# SrcBackplane01_7slots.net
KiCad netlist of a schematic drawn in EAGLE
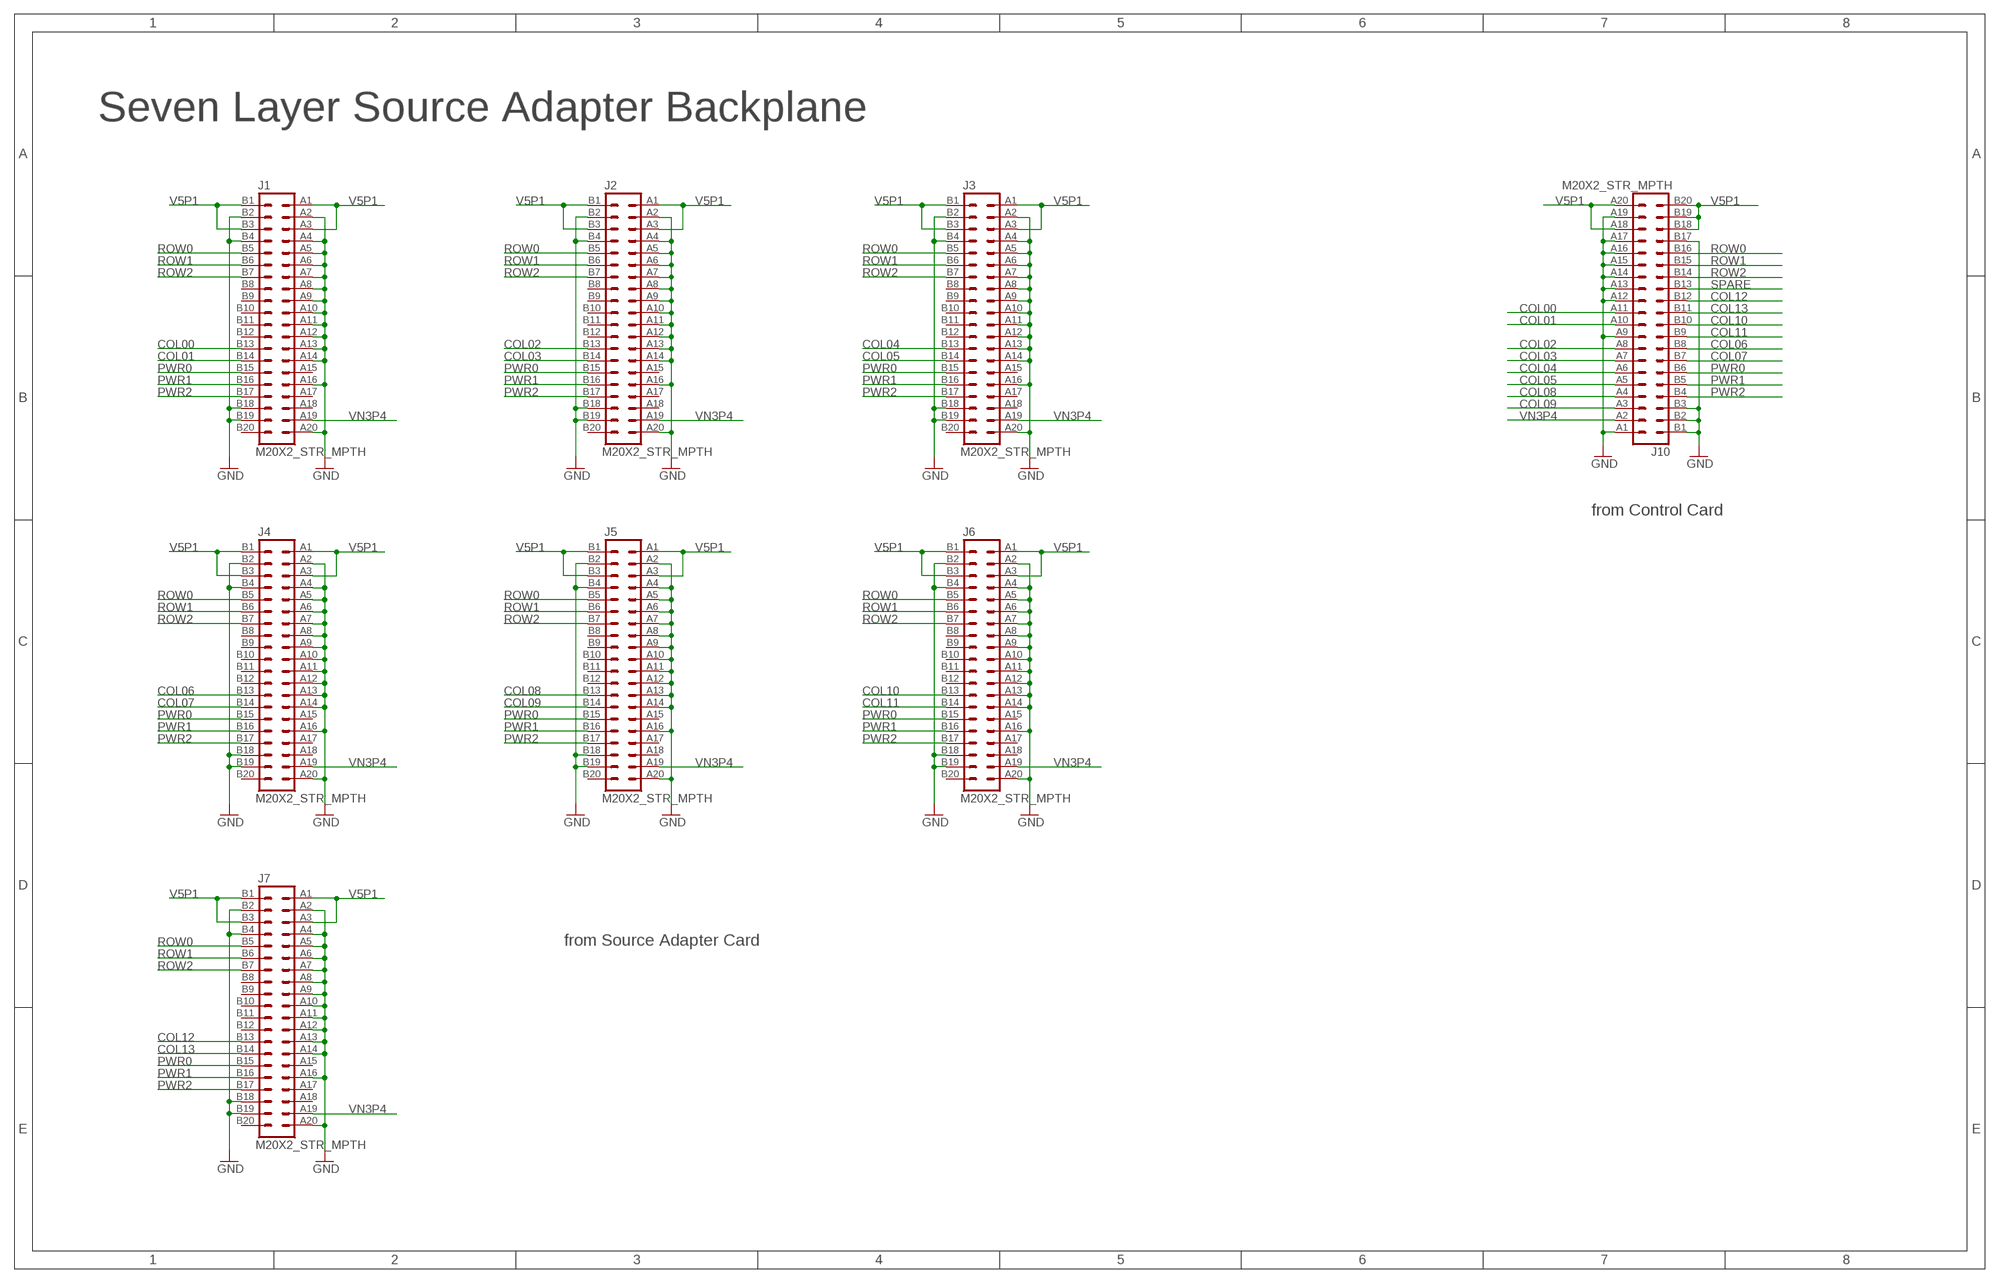
[diagram p0: schematic, sheet 1]

(export (version "E")
  (design (tool "Eeschema 10.0.6"))
  (components
    (comp (ref "J1")
      (value "M20X2_STR_MPTH")
      (footprint "eagle-import:M20X2_HARFLEX_F_STR_MPTH")
      (libsource (lib "eagle-import") (part "M20X2_STR_MPTH"))
    )
    (comp (ref "J2")
      (value "M20X2_STR_MPTH")
      (footprint "eagle-import:M20X2_HARFLEX_F_STR_MPTH")
      (libsource (lib "eagle-import") (part "M20X2_STR_MPTH"))
    )
    (comp (ref "J3")
      (value "M20X2_STR_MPTH")
      (footprint "eagle-import:M20X2_HARFLEX_F_STR_MPTH")
      (libsource (lib "eagle-import") (part "M20X2_STR_MPTH"))
    )
    (comp (ref "J4")
      (value "M20X2_STR_MPTH")
      (footprint "eagle-import:M20X2_HARFLEX_F_STR_MPTH")
      (libsource (lib "eagle-import") (part "M20X2_STR_MPTH"))
    )
    (comp (ref "J5")
      (value "M20X2_STR_MPTH")
      (footprint "eagle-import:M20X2_HARFLEX_F_STR_MPTH")
      (libsource (lib "eagle-import") (part "M20X2_STR_MPTH"))
    )
    (comp (ref "J6")
      (value "M20X2_STR_MPTH")
      (footprint "eagle-import:M20X2_HARFLEX_F_STR_MPTH")
      (libsource (lib "eagle-import") (part "M20X2_STR_MPTH"))
    )
    (comp (ref "J7")
      (value "M20X2_STR_MPTH")
      (footprint "eagle-import:M20X2_HARFLEX_F_STR_MPTH")
      (libsource (lib "eagle-import") (part "M20X2_STR_MPTH"))
    )
    (comp (ref "J10")
      (value "M20X2_STR_MPTH")
      (footprint "eagle-import:M20X2_HARFLEX_F_STR_MPTH")
      (libsource (lib "eagle-import") (part "M20X2_STR_MPTH"))
    )
  )
  (nets
    (net (code "1") (name "/COL00") (class "Default")
      (node (ref "J1") (pin "B13") (pinfunction "25_B13") (pintype "passive"))
      (node (ref "J10") (pin "A11") (pinfunction "22_A11") (pintype "passive"))
    )
    (net (code "2") (name "/COL01") (class "Default")
      (node (ref "J1") (pin "B14") (pinfunction "27_B14") (pintype "passive"))
      (node (ref "J10") (pin "A10") (pinfunction "20_A10") (pintype "passive"))
    )
    (net (code "3") (name "/COL02") (class "Default")
      (node (ref "J10") (pin "A8") (pinfunction "16_A8") (pintype "passive"))
      (node (ref "J2") (pin "B13") (pinfunction "25_B13") (pintype "passive"))
    )
    (net (code "4") (name "/COL03") (class "Default")
      (node (ref "J10") (pin "A7") (pinfunction "14_A7") (pintype "passive"))
      (node (ref "J2") (pin "B14") (pinfunction "27_B14") (pintype "passive"))
    )
    (net (code "5") (name "/COL04") (class "Default")
      (node (ref "J10") (pin "A6") (pinfunction "12_A6") (pintype "passive"))
      (node (ref "J3") (pin "B13") (pinfunction "25_B13") (pintype "passive"))
    )
    (net (code "6") (name "/COL05") (class "Default")
      (node (ref "J10") (pin "A5") (pinfunction "10_A5") (pintype "passive"))
      (node (ref "J3") (pin "B14") (pinfunction "27_B14") (pintype "passive"))
    )
    (net (code "7") (name "/COL06") (class "Default")
      (node (ref "J10") (pin "B8") (pinfunction "15_B8") (pintype "passive"))
      (node (ref "J4") (pin "B13") (pinfunction "25_B13") (pintype "passive"))
    )
    (net (code "8") (name "/COL07") (class "Default")
      (node (ref "J10") (pin "B7") (pinfunction "13_B7") (pintype "passive"))
      (node (ref "J4") (pin "B14") (pinfunction "27_B14") (pintype "passive"))
    )
    (net (code "9") (name "/COL08") (class "Default")
      (node (ref "J10") (pin "A4") (pinfunction "8_A4") (pintype "passive"))
      (node (ref "J5") (pin "B13") (pinfunction "25_B13") (pintype "passive"))
    )
    (net (code "10") (name "/COL09") (class "Default")
      (node (ref "J10") (pin "A3") (pinfunction "6_A3") (pintype "passive"))
      (node (ref "J5") (pin "B14") (pinfunction "27_B14") (pintype "passive"))
    )
    (net (code "11") (name "/COL10") (class "Default")
      (node (ref "J10") (pin "B10") (pinfunction "19_B10") (pintype "passive"))
      (node (ref "J6") (pin "B13") (pinfunction "25_B13") (pintype "passive"))
    )
    (net (code "12") (name "/COL11") (class "Default")
      (node (ref "J10") (pin "B9") (pinfunction "17_B9") (pintype "passive"))
      (node (ref "J6") (pin "B14") (pinfunction "27_B14") (pintype "passive"))
    )
    (net (code "13") (name "/COL12") (class "Default")
      (node (ref "J10") (pin "B12") (pinfunction "23_B12") (pintype "passive"))
      (node (ref "J7") (pin "B13") (pinfunction "25_B13") (pintype "passive"))
    )
    (net (code "14") (name "/COL13") (class "Default")
      (node (ref "J10") (pin "B11") (pinfunction "21_B11") (pintype "passive"))
      (node (ref "J7") (pin "B14") (pinfunction "27_B14") (pintype "passive"))
    )
    (net (code "15") (name "/PWR0") (class "Default")
      (node (ref "J1") (pin "B15") (pinfunction "29_B15") (pintype "passive"))
      (node (ref "J10") (pin "B6") (pinfunction "11_B6") (pintype "passive"))
      (node (ref "J2") (pin "B15") (pinfunction "29_B15") (pintype "passive"))
      (node (ref "J3") (pin "B15") (pinfunction "29_B15") (pintype "passive"))
      (node (ref "J4") (pin "B15") (pinfunction "29_B15") (pintype "passive"))
      (node (ref "J5") (pin "B15") (pinfunction "29_B15") (pintype "passive"))
      (node (ref "J6") (pin "B15") (pinfunction "29_B15") (pintype "passive"))
      (node (ref "J7") (pin "B15") (pinfunction "29_B15") (pintype "passive"))
    )
    (net (code "16") (name "/PWR1") (class "Default")
      (node (ref "J1") (pin "B16") (pinfunction "31_B16") (pintype "passive"))
      (node (ref "J10") (pin "B5") (pinfunction "9_B5") (pintype "passive"))
      (node (ref "J2") (pin "B16") (pinfunction "31_B16") (pintype "passive"))
      (node (ref "J3") (pin "B16") (pinfunction "31_B16") (pintype "passive"))
      (node (ref "J4") (pin "B16") (pinfunction "31_B16") (pintype "passive"))
      (node (ref "J5") (pin "B16") (pinfunction "31_B16") (pintype "passive"))
      (node (ref "J6") (pin "B16") (pinfunction "31_B16") (pintype "passive"))
      (node (ref "J7") (pin "B16") (pinfunction "31_B16") (pintype "passive"))
    )
    (net (code "17") (name "/PWR2") (class "Default")
      (node (ref "J1") (pin "B17") (pinfunction "33_B17") (pintype "passive"))
      (node (ref "J10") (pin "B4") (pinfunction "7_B4") (pintype "passive"))
      (node (ref "J2") (pin "B17") (pinfunction "33_B17") (pintype "passive"))
      (node (ref "J3") (pin "B17") (pinfunction "33_B17") (pintype "passive"))
      (node (ref "J4") (pin "B17") (pinfunction "33_B17") (pintype "passive"))
      (node (ref "J5") (pin "B17") (pinfunction "33_B17") (pintype "passive"))
      (node (ref "J6") (pin "B17") (pinfunction "33_B17") (pintype "passive"))
      (node (ref "J7") (pin "B17") (pinfunction "33_B17") (pintype "passive"))
    )
    (net (code "18") (name "/ROW0") (class "Default")
      (node (ref "J1") (pin "B5") (pinfunction "9_B5") (pintype "passive"))
      (node (ref "J10") (pin "B16") (pinfunction "31_B16") (pintype "passive"))
      (node (ref "J2") (pin "B5") (pinfunction "9_B5") (pintype "passive"))
      (node (ref "J3") (pin "B5") (pinfunction "9_B5") (pintype "passive"))
      (node (ref "J4") (pin "B5") (pinfunction "9_B5") (pintype "passive"))
      (node (ref "J5") (pin "B5") (pinfunction "9_B5") (pintype "passive"))
      (node (ref "J6") (pin "B5") (pinfunction "9_B5") (pintype "passive"))
      (node (ref "J7") (pin "B5") (pinfunction "9_B5") (pintype "passive"))
    )
    (net (code "19") (name "/ROW1") (class "Default")
      (node (ref "J1") (pin "B6") (pinfunction "11_B6") (pintype "passive"))
      (node (ref "J10") (pin "B15") (pinfunction "29_B15") (pintype "passive"))
      (node (ref "J2") (pin "B6") (pinfunction "11_B6") (pintype "passive"))
      (node (ref "J3") (pin "B6") (pinfunction "11_B6") (pintype "passive"))
      (node (ref "J4") (pin "B6") (pinfunction "11_B6") (pintype "passive"))
      (node (ref "J5") (pin "B6") (pinfunction "11_B6") (pintype "passive"))
      (node (ref "J6") (pin "B6") (pinfunction "11_B6") (pintype "passive"))
      (node (ref "J7") (pin "B6") (pinfunction "11_B6") (pintype "passive"))
    )
    (net (code "20") (name "/ROW2") (class "Default")
      (node (ref "J1") (pin "B7") (pinfunction "13_B7") (pintype "passive"))
      (node (ref "J10") (pin "B14") (pinfunction "27_B14") (pintype "passive"))
      (node (ref "J2") (pin "B7") (pinfunction "13_B7") (pintype "passive"))
      (node (ref "J3") (pin "B7") (pinfunction "13_B7") (pintype "passive"))
      (node (ref "J4") (pin "B7") (pinfunction "13_B7") (pintype "passive"))
      (node (ref "J5") (pin "B7") (pinfunction "13_B7") (pintype "passive"))
      (node (ref "J6") (pin "B7") (pinfunction "13_B7") (pintype "passive"))
      (node (ref "J7") (pin "B7") (pinfunction "13_B7") (pintype "passive"))
    )
    (net (code "21") (name "/SPARE") (class "Default")
      (node (ref "J10") (pin "B13") (pinfunction "25_B13") (pintype "passive"))
    )
    (net (code "22") (name "/V5P1") (class "Default")
      (node (ref "J1") (pin "A1") (pinfunction "2_A1") (pintype "passive"))
      (node (ref "J1") (pin "A3") (pinfunction "6_A3") (pintype "passive"))
      (node (ref "J1") (pin "B1") (pinfunction "1_B1") (pintype "passive"))
      (node (ref "J1") (pin "B3") (pinfunction "5_B3") (pintype "passive"))
      (node (ref "J10") (pin "A18") (pinfunction "36_A18") (pintype "passive"))
      (node (ref "J10") (pin "A20") (pinfunction "40_A20") (pintype "passive"))
      (node (ref "J10") (pin "B18") (pinfunction "35_B18") (pintype "passive"))
      (node (ref "J10") (pin "B19") (pinfunction "37_B19") (pintype "passive"))
      (node (ref "J10") (pin "B20") (pinfunction "39_B20") (pintype "passive"))
      (node (ref "J2") (pin "A1") (pinfunction "2_A1") (pintype "passive"))
      (node (ref "J2") (pin "A3") (pinfunction "6_A3") (pintype "passive"))
      (node (ref "J2") (pin "B1") (pinfunction "1_B1") (pintype "passive"))
      (node (ref "J2") (pin "B3") (pinfunction "5_B3") (pintype "passive"))
      (node (ref "J3") (pin "A1") (pinfunction "2_A1") (pintype "passive"))
      (node (ref "J3") (pin "A3") (pinfunction "6_A3") (pintype "passive"))
      (node (ref "J3") (pin "B1") (pinfunction "1_B1") (pintype "passive"))
      (node (ref "J3") (pin "B3") (pinfunction "5_B3") (pintype "passive"))
      (node (ref "J4") (pin "A1") (pinfunction "2_A1") (pintype "passive"))
      (node (ref "J4") (pin "A3") (pinfunction "6_A3") (pintype "passive"))
      (node (ref "J4") (pin "B1") (pinfunction "1_B1") (pintype "passive"))
      (node (ref "J4") (pin "B3") (pinfunction "5_B3") (pintype "passive"))
      (node (ref "J5") (pin "A1") (pinfunction "2_A1") (pintype "passive"))
      (node (ref "J5") (pin "A3") (pinfunction "6_A3") (pintype "passive"))
      (node (ref "J5") (pin "B1") (pinfunction "1_B1") (pintype "passive"))
      (node (ref "J5") (pin "B3") (pinfunction "5_B3") (pintype "passive"))
      (node (ref "J6") (pin "A1") (pinfunction "2_A1") (pintype "passive"))
      (node (ref "J6") (pin "A3") (pinfunction "6_A3") (pintype "passive"))
      (node (ref "J6") (pin "B1") (pinfunction "1_B1") (pintype "passive"))
      (node (ref "J6") (pin "B3") (pinfunction "5_B3") (pintype "passive"))
      (node (ref "J7") (pin "A1") (pinfunction "2_A1") (pintype "passive"))
      (node (ref "J7") (pin "A3") (pinfunction "6_A3") (pintype "passive"))
      (node (ref "J7") (pin "B1") (pinfunction "1_B1") (pintype "passive"))
      (node (ref "J7") (pin "B3") (pinfunction "5_B3") (pintype "passive"))
    )
    (net (code "23") (name "/VN3P4") (class "Default")
      (node (ref "J1") (pin "A19") (pinfunction "38_A19") (pintype "passive"))
      (node (ref "J10") (pin "A2") (pinfunction "4_A2") (pintype "passive"))
      (node (ref "J2") (pin "A19") (pinfunction "38_A19") (pintype "passive"))
      (node (ref "J3") (pin "A19") (pinfunction "38_A19") (pintype "passive"))
      (node (ref "J4") (pin "A19") (pinfunction "38_A19") (pintype "passive"))
      (node (ref "J5") (pin "A19") (pinfunction "38_A19") (pintype "passive"))
      (node (ref "J6") (pin "A19") (pinfunction "38_A19") (pintype "passive"))
      (node (ref "J7") (pin "A19") (pinfunction "38_A19") (pintype "passive"))
    )
    (net (code "24") (name "GND") (class "Default")
      (node (ref "J1") (pin "A10") (pinfunction "20_A10") (pintype "passive"))
      (node (ref "J1") (pin "A11") (pinfunction "22_A11") (pintype "passive"))
      (node (ref "J1") (pin "A12") (pinfunction "24_A12") (pintype "passive"))
      (node (ref "J1") (pin "A13") (pinfunction "26_A13") (pintype "passive"))
      (node (ref "J1") (pin "A14") (pinfunction "28_A14") (pintype "passive"))
      (node (ref "J1") (pin "A16") (pinfunction "32_A16") (pintype "passive"))
      (node (ref "J1") (pin "A2") (pinfunction "4_A2") (pintype "passive"))
      (node (ref "J1") (pin "A20") (pinfunction "40_A20") (pintype "passive"))
      (node (ref "J1") (pin "A4") (pinfunction "8_A4") (pintype "passive"))
      (node (ref "J1") (pin "A5") (pinfunction "10_A5") (pintype "passive"))
      (node (ref "J1") (pin "A6") (pinfunction "12_A6") (pintype "passive"))
      (node (ref "J1") (pin "A7") (pinfunction "14_A7") (pintype "passive"))
      (node (ref "J1") (pin "A8") (pinfunction "16_A8") (pintype "passive"))
      (node (ref "J1") (pin "A9") (pinfunction "18_A9") (pintype "passive"))
      (node (ref "J1") (pin "B18") (pinfunction "35_B18") (pintype "passive"))
      (node (ref "J1") (pin "B19") (pinfunction "37_B19") (pintype "passive"))
      (node (ref "J1") (pin "B2") (pinfunction "3_B2") (pintype "passive"))
      (node (ref "J1") (pin "B4") (pinfunction "7_B4") (pintype "passive"))
      (node (ref "J10") (pin "A1") (pinfunction "2_A1") (pintype "passive"))
      (node (ref "J10") (pin "A12") (pinfunction "24_A12") (pintype "passive"))
      (node (ref "J10") (pin "A13") (pinfunction "26_A13") (pintype "passive"))
      (node (ref "J10") (pin "A14") (pinfunction "28_A14") (pintype "passive"))
      (node (ref "J10") (pin "A15") (pinfunction "30_A15") (pintype "passive"))
      (node (ref "J10") (pin "A16") (pinfunction "32_A16") (pintype "passive"))
      (node (ref "J10") (pin "A17") (pinfunction "34_A17") (pintype "passive"))
      (node (ref "J10") (pin "A19") (pinfunction "38_A19") (pintype "passive"))
      (node (ref "J10") (pin "A9") (pinfunction "18_A9") (pintype "passive"))
      (node (ref "J10") (pin "B1") (pinfunction "1_B1") (pintype "passive"))
      (node (ref "J10") (pin "B17") (pinfunction "33_B17") (pintype "passive"))
      (node (ref "J10") (pin "B2") (pinfunction "3_B2") (pintype "passive"))
      (node (ref "J10") (pin "B3") (pinfunction "5_B3") (pintype "passive"))
      (node (ref "J2") (pin "A10") (pinfunction "20_A10") (pintype "passive"))
      (node (ref "J2") (pin "A11") (pinfunction "22_A11") (pintype "passive"))
      (node (ref "J2") (pin "A12") (pinfunction "24_A12") (pintype "passive"))
      (node (ref "J2") (pin "A13") (pinfunction "26_A13") (pintype "passive"))
      (node (ref "J2") (pin "A14") (pinfunction "28_A14") (pintype "passive"))
      (node (ref "J2") (pin "A16") (pinfunction "32_A16") (pintype "passive"))
      (node (ref "J2") (pin "A2") (pinfunction "4_A2") (pintype "passive"))
      (node (ref "J2") (pin "A20") (pinfunction "40_A20") (pintype "passive"))
      (node (ref "J2") (pin "A4") (pinfunction "8_A4") (pintype "passive"))
      (node (ref "J2") (pin "A5") (pinfunction "10_A5") (pintype "passive"))
      (node (ref "J2") (pin "A6") (pinfunction "12_A6") (pintype "passive"))
      (node (ref "J2") (pin "A7") (pinfunction "14_A7") (pintype "passive"))
      (node (ref "J2") (pin "A8") (pinfunction "16_A8") (pintype "passive"))
      (node (ref "J2") (pin "A9") (pinfunction "18_A9") (pintype "passive"))
      (node (ref "J2") (pin "B18") (pinfunction "35_B18") (pintype "passive"))
      (node (ref "J2") (pin "B19") (pinfunction "37_B19") (pintype "passive"))
      (node (ref "J2") (pin "B2") (pinfunction "3_B2") (pintype "passive"))
      (node (ref "J2") (pin "B4") (pinfunction "7_B4") (pintype "passive"))
      (node (ref "J3") (pin "A10") (pinfunction "20_A10") (pintype "passive"))
      (node (ref "J3") (pin "A11") (pinfunction "22_A11") (pintype "passive"))
      (node (ref "J3") (pin "A12") (pinfunction "24_A12") (pintype "passive"))
      (node (ref "J3") (pin "A13") (pinfunction "26_A13") (pintype "passive"))
      (node (ref "J3") (pin "A14") (pinfunction "28_A14") (pintype "passive"))
      (node (ref "J3") (pin "A16") (pinfunction "32_A16") (pintype "passive"))
      (node (ref "J3") (pin "A2") (pinfunction "4_A2") (pintype "passive"))
      (node (ref "J3") (pin "A20") (pinfunction "40_A20") (pintype "passive"))
      (node (ref "J3") (pin "A4") (pinfunction "8_A4") (pintype "passive"))
      (node (ref "J3") (pin "A5") (pinfunction "10_A5") (pintype "passive"))
      (node (ref "J3") (pin "A6") (pinfunction "12_A6") (pintype "passive"))
      (node (ref "J3") (pin "A7") (pinfunction "14_A7") (pintype "passive"))
      (node (ref "J3") (pin "A8") (pinfunction "16_A8") (pintype "passive"))
      (node (ref "J3") (pin "A9") (pinfunction "18_A9") (pintype "passive"))
      (node (ref "J3") (pin "B18") (pinfunction "35_B18") (pintype "passive"))
      (node (ref "J3") (pin "B19") (pinfunction "37_B19") (pintype "passive"))
      (node (ref "J3") (pin "B2") (pinfunction "3_B2") (pintype "passive"))
      (node (ref "J3") (pin "B4") (pinfunction "7_B4") (pintype "passive"))
      (node (ref "J4") (pin "A10") (pinfunction "20_A10") (pintype "passive"))
      (node (ref "J4") (pin "A11") (pinfunction "22_A11") (pintype "passive"))
      (node (ref "J4") (pin "A12") (pinfunction "24_A12") (pintype "passive"))
      (node (ref "J4") (pin "A13") (pinfunction "26_A13") (pintype "passive"))
      (node (ref "J4") (pin "A14") (pinfunction "28_A14") (pintype "passive"))
      (node (ref "J4") (pin "A16") (pinfunction "32_A16") (pintype "passive"))
      (node (ref "J4") (pin "A2") (pinfunction "4_A2") (pintype "passive"))
      (node (ref "J4") (pin "A20") (pinfunction "40_A20") (pintype "passive"))
      (node (ref "J4") (pin "A4") (pinfunction "8_A4") (pintype "passive"))
      (node (ref "J4") (pin "A5") (pinfunction "10_A5") (pintype "passive"))
      (node (ref "J4") (pin "A6") (pinfunction "12_A6") (pintype "passive"))
      (node (ref "J4") (pin "A7") (pinfunction "14_A7") (pintype "passive"))
      (node (ref "J4") (pin "A8") (pinfunction "16_A8") (pintype "passive"))
      (node (ref "J4") (pin "A9") (pinfunction "18_A9") (pintype "passive"))
      (node (ref "J4") (pin "B18") (pinfunction "35_B18") (pintype "passive"))
      (node (ref "J4") (pin "B19") (pinfunction "37_B19") (pintype "passive"))
      (node (ref "J4") (pin "B2") (pinfunction "3_B2") (pintype "passive"))
      (node (ref "J4") (pin "B4") (pinfunction "7_B4") (pintype "passive"))
      (node (ref "J5") (pin "A10") (pinfunction "20_A10") (pintype "passive"))
      (node (ref "J5") (pin "A11") (pinfunction "22_A11") (pintype "passive"))
      (node (ref "J5") (pin "A12") (pinfunction "24_A12") (pintype "passive"))
      (node (ref "J5") (pin "A13") (pinfunction "26_A13") (pintype "passive"))
      (node (ref "J5") (pin "A14") (pinfunction "28_A14") (pintype "passive"))
      (node (ref "J5") (pin "A16") (pinfunction "32_A16") (pintype "passive"))
      (node (ref "J5") (pin "A2") (pinfunction "4_A2") (pintype "passive"))
      (node (ref "J5") (pin "A20") (pinfunction "40_A20") (pintype "passive"))
      (node (ref "J5") (pin "A4") (pinfunction "8_A4") (pintype "passive"))
      (node (ref "J5") (pin "A5") (pinfunction "10_A5") (pintype "passive"))
      (node (ref "J5") (pin "A6") (pinfunction "12_A6") (pintype "passive"))
      (node (ref "J5") (pin "A7") (pinfunction "14_A7") (pintype "passive"))
      (node (ref "J5") (pin "A8") (pinfunction "16_A8") (pintype "passive"))
      (node (ref "J5") (pin "A9") (pinfunction "18_A9") (pintype "passive"))
      (node (ref "J5") (pin "B18") (pinfunction "35_B18") (pintype "passive"))
      (node (ref "J5") (pin "B19") (pinfunction "37_B19") (pintype "passive"))
      (node (ref "J5") (pin "B2") (pinfunction "3_B2") (pintype "passive"))
      (node (ref "J5") (pin "B4") (pinfunction "7_B4") (pintype "passive"))
      (node (ref "J6") (pin "A10") (pinfunction "20_A10") (pintype "passive"))
      (node (ref "J6") (pin "A11") (pinfunction "22_A11") (pintype "passive"))
      (node (ref "J6") (pin "A12") (pinfunction "24_A12") (pintype "passive"))
      (node (ref "J6") (pin "A13") (pinfunction "26_A13") (pintype "passive"))
      (node (ref "J6") (pin "A14") (pinfunction "28_A14") (pintype "passive"))
      (node (ref "J6") (pin "A16") (pinfunction "32_A16") (pintype "passive"))
      (node (ref "J6") (pin "A2") (pinfunction "4_A2") (pintype "passive"))
      (node (ref "J6") (pin "A20") (pinfunction "40_A20") (pintype "passive"))
      (node (ref "J6") (pin "A4") (pinfunction "8_A4") (pintype "passive"))
      (node (ref "J6") (pin "A5") (pinfunction "10_A5") (pintype "passive"))
      (node (ref "J6") (pin "A6") (pinfunction "12_A6") (pintype "passive"))
      (node (ref "J6") (pin "A7") (pinfunction "14_A7") (pintype "passive"))
      (node (ref "J6") (pin "A8") (pinfunction "16_A8") (pintype "passive"))
      (node (ref "J6") (pin "A9") (pinfunction "18_A9") (pintype "passive"))
      (node (ref "J6") (pin "B18") (pinfunction "35_B18") (pintype "passive"))
      (node (ref "J6") (pin "B19") (pinfunction "37_B19") (pintype "passive"))
      (node (ref "J6") (pin "B2") (pinfunction "3_B2") (pintype "passive"))
      (node (ref "J6") (pin "B4") (pinfunction "7_B4") (pintype "passive"))
      (node (ref "J7") (pin "A10") (pinfunction "20_A10") (pintype "passive"))
      (node (ref "J7") (pin "A11") (pinfunction "22_A11") (pintype "passive"))
      (node (ref "J7") (pin "A12") (pinfunction "24_A12") (pintype "passive"))
      (node (ref "J7") (pin "A13") (pinfunction "26_A13") (pintype "passive"))
      (node (ref "J7") (pin "A14") (pinfunction "28_A14") (pintype "passive"))
      (node (ref "J7") (pin "A16") (pinfunction "32_A16") (pintype "passive"))
      (node (ref "J7") (pin "A2") (pinfunction "4_A2") (pintype "passive"))
      (node (ref "J7") (pin "A20") (pinfunction "40_A20") (pintype "passive"))
      (node (ref "J7") (pin "A4") (pinfunction "8_A4") (pintype "passive"))
      (node (ref "J7") (pin "A5") (pinfunction "10_A5") (pintype "passive"))
      (node (ref "J7") (pin "A6") (pinfunction "12_A6") (pintype "passive"))
      (node (ref "J7") (pin "A7") (pinfunction "14_A7") (pintype "passive"))
      (node (ref "J7") (pin "A8") (pinfunction "16_A8") (pintype "passive"))
      (node (ref "J7") (pin "A9") (pinfunction "18_A9") (pintype "passive"))
      (node (ref "J7") (pin "B18") (pinfunction "35_B18") (pintype "passive"))
      (node (ref "J7") (pin "B19") (pinfunction "37_B19") (pintype "passive"))
      (node (ref "J7") (pin "B2") (pinfunction "3_B2") (pintype "passive"))
      (node (ref "J7") (pin "B4") (pinfunction "7_B4") (pintype "passive"))
    )
    (net (code "25") (name "unconnected-(J1-15-PadB8)") (class "Default")
      (node (ref "J1") (pin "B8") (pinfunction "15_B8") (pintype "passive"))
    )
    (net (code "26") (name "unconnected-(J1-17-PadB9)") (class "Default")
      (node (ref "J1") (pin "B9") (pinfunction "17_B9") (pintype "passive"))
    )
    (net (code "27") (name "unconnected-(J1-19-PadB10)") (class "Default")
      (node (ref "J1") (pin "B10") (pinfunction "19_B10") (pintype "passive"))
    )
    (net (code "28") (name "unconnected-(J1-21-PadB11)") (class "Default")
      (node (ref "J1") (pin "B11") (pinfunction "21_B11") (pintype "passive"))
    )
    (net (code "29") (name "unconnected-(J1-23-PadB12)") (class "Default")
      (node (ref "J1") (pin "B12") (pinfunction "23_B12") (pintype "passive"))
    )
    (net (code "30") (name "unconnected-(J1-30-PadA15)") (class "Default")
      (node (ref "J1") (pin "A15") (pinfunction "30_A15") (pintype "passive"))
    )
    (net (code "31") (name "unconnected-(J1-34-PadA17)") (class "Default")
      (node (ref "J1") (pin "A17") (pinfunction "34_A17") (pintype "passive"))
    )
    (net (code "32") (name "unconnected-(J1-36-PadA18)") (class "Default")
      (node (ref "J1") (pin "A18") (pinfunction "36_A18") (pintype "passive"))
    )
    (net (code "33") (name "unconnected-(J1-39-PadB20)") (class "Default")
      (node (ref "J1") (pin "B20") (pinfunction "39_B20") (pintype "passive"))
    )
    (net (code "34") (name "unconnected-(J2-15-PadB8)") (class "Default")
      (node (ref "J2") (pin "B8") (pinfunction "15_B8") (pintype "passive"))
    )
    (net (code "35") (name "unconnected-(J2-17-PadB9)") (class "Default")
      (node (ref "J2") (pin "B9") (pinfunction "17_B9") (pintype "passive"))
    )
    (net (code "36") (name "unconnected-(J2-19-PadB10)") (class "Default")
      (node (ref "J2") (pin "B10") (pinfunction "19_B10") (pintype "passive"))
    )
    (net (code "37") (name "unconnected-(J2-21-PadB11)") (class "Default")
      (node (ref "J2") (pin "B11") (pinfunction "21_B11") (pintype "passive"))
    )
    (net (code "38") (name "unconnected-(J2-23-PadB12)") (class "Default")
      (node (ref "J2") (pin "B12") (pinfunction "23_B12") (pintype "passive"))
    )
    (net (code "39") (name "unconnected-(J2-30-PadA15)") (class "Default")
      (node (ref "J2") (pin "A15") (pinfunction "30_A15") (pintype "passive"))
    )
    (net (code "40") (name "unconnected-(J2-34-PadA17)") (class "Default")
      (node (ref "J2") (pin "A17") (pinfunction "34_A17") (pintype "passive"))
    )
    (net (code "41") (name "unconnected-(J2-36-PadA18)") (class "Default")
      (node (ref "J2") (pin "A18") (pinfunction "36_A18") (pintype "passive"))
    )
    (net (code "42") (name "unconnected-(J2-39-PadB20)") (class "Default")
      (node (ref "J2") (pin "B20") (pinfunction "39_B20") (pintype "passive"))
    )
    (net (code "43") (name "unconnected-(J3-15-PadB8)") (class "Default")
      (node (ref "J3") (pin "B8") (pinfunction "15_B8") (pintype "passive"))
    )
    (net (code "44") (name "unconnected-(J3-17-PadB9)") (class "Default")
      (node (ref "J3") (pin "B9") (pinfunction "17_B9") (pintype "passive"))
    )
    (net (code "45") (name "unconnected-(J3-19-PadB10)") (class "Default")
      (node (ref "J3") (pin "B10") (pinfunction "19_B10") (pintype "passive"))
    )
    (net (code "46") (name "unconnected-(J3-21-PadB11)") (class "Default")
      (node (ref "J3") (pin "B11") (pinfunction "21_B11") (pintype "passive"))
    )
    (net (code "47") (name "unconnected-(J3-23-PadB12)") (class "Default")
      (node (ref "J3") (pin "B12") (pinfunction "23_B12") (pintype "passive"))
    )
    (net (code "48") (name "unconnected-(J3-30-PadA15)") (class "Default")
      (node (ref "J3") (pin "A15") (pinfunction "30_A15") (pintype "passive"))
    )
    (net (code "49") (name "unconnected-(J3-34-PadA17)") (class "Default")
      (node (ref "J3") (pin "A17") (pinfunction "34_A17") (pintype "passive"))
    )
    (net (code "50") (name "unconnected-(J3-36-PadA18)") (class "Default")
      (node (ref "J3") (pin "A18") (pinfunction "36_A18") (pintype "passive"))
    )
    (net (code "51") (name "unconnected-(J3-39-PadB20)") (class "Default")
      (node (ref "J3") (pin "B20") (pinfunction "39_B20") (pintype "passive"))
    )
    (net (code "52") (name "unconnected-(J4-15-PadB8)") (class "Default")
      (node (ref "J4") (pin "B8") (pinfunction "15_B8") (pintype "passive"))
    )
    (net (code "53") (name "unconnected-(J4-17-PadB9)") (class "Default")
      (node (ref "J4") (pin "B9") (pinfunction "17_B9") (pintype "passive"))
    )
    (net (code "54") (name "unconnected-(J4-19-PadB10)") (class "Default")
      (node (ref "J4") (pin "B10") (pinfunction "19_B10") (pintype "passive"))
    )
    (net (code "55") (name "unconnected-(J4-21-PadB11)") (class "Default")
      (node (ref "J4") (pin "B11") (pinfunction "21_B11") (pintype "passive"))
    )
    (net (code "56") (name "unconnected-(J4-23-PadB12)") (class "Default")
      (node (ref "J4") (pin "B12") (pinfunction "23_B12") (pintype "passive"))
    )
    (net (code "57") (name "unconnected-(J4-30-PadA15)") (class "Default")
      (node (ref "J4") (pin "A15") (pinfunction "30_A15") (pintype "passive"))
    )
    (net (code "58") (name "unconnected-(J4-34-PadA17)") (class "Default")
      (node (ref "J4") (pin "A17") (pinfunction "34_A17") (pintype "passive"))
    )
    (net (code "59") (name "unconnected-(J4-36-PadA18)") (class "Default")
      (node (ref "J4") (pin "A18") (pinfunction "36_A18") (pintype "passive"))
    )
    (net (code "60") (name "unconnected-(J4-39-PadB20)") (class "Default")
      (node (ref "J4") (pin "B20") (pinfunction "39_B20") (pintype "passive"))
    )
    (net (code "61") (name "unconnected-(J5-15-PadB8)") (class "Default")
      (node (ref "J5") (pin "B8") (pinfunction "15_B8") (pintype "passive"))
    )
    (net (code "62") (name "unconnected-(J5-17-PadB9)") (class "Default")
      (node (ref "J5") (pin "B9") (pinfunction "17_B9") (pintype "passive"))
    )
    (net (code "63") (name "unconnected-(J5-19-PadB10)") (class "Default")
      (node (ref "J5") (pin "B10") (pinfunction "19_B10") (pintype "passive"))
    )
    (net (code "64") (name "unconnected-(J5-21-PadB11)") (class "Default")
      (node (ref "J5") (pin "B11") (pinfunction "21_B11") (pintype "passive"))
    )
    (net (code "65") (name "unconnected-(J5-23-PadB12)") (class "Default")
      (node (ref "J5") (pin "B12") (pinfunction "23_B12") (pintype "passive"))
    )
    (net (code "66") (name "unconnected-(J5-30-PadA15)") (class "Default")
      (node (ref "J5") (pin "A15") (pinfunction "30_A15") (pintype "passive"))
    )
    (net (code "67") (name "unconnected-(J5-34-PadA17)") (class "Default")
      (node (ref "J5") (pin "A17") (pinfunction "34_A17") (pintype "passive"))
    )
    (net (code "68") (name "unconnected-(J5-36-PadA18)") (class "Default")
      (node (ref "J5") (pin "A18") (pinfunction "36_A18") (pintype "passive"))
    )
    (net (code "69") (name "unconnected-(J5-39-PadB20)") (class "Default")
      (node (ref "J5") (pin "B20") (pinfunction "39_B20") (pintype "passive"))
    )
    (net (code "70") (name "unconnected-(J6-15-PadB8)") (class "Default")
      (node (ref "J6") (pin "B8") (pinfunction "15_B8") (pintype "passive"))
    )
    (net (code "71") (name "unconnected-(J6-17-PadB9)") (class "Default")
      (node (ref "J6") (pin "B9") (pinfunction "17_B9") (pintype "passive"))
    )
    (net (code "72") (name "unconnected-(J6-19-PadB10)") (class "Default")
      (node (ref "J6") (pin "B10") (pinfunction "19_B10") (pintype "passive"))
    )
    (net (code "73") (name "unconnected-(J6-21-PadB11)") (class "Default")
      (node (ref "J6") (pin "B11") (pinfunction "21_B11") (pintype "passive"))
    )
    (net (code "74") (name "unconnected-(J6-23-PadB12)") (class "Default")
      (node (ref "J6") (pin "B12") (pinfunction "23_B12") (pintype "passive"))
    )
    (net (code "75") (name "unconnected-(J6-30-PadA15)") (class "Default")
      (node (ref "J6") (pin "A15") (pinfunction "30_A15") (pintype "passive"))
    )
    (net (code "76") (name "unconnected-(J6-34-PadA17)") (class "Default")
      (node (ref "J6") (pin "A17") (pinfunction "34_A17") (pintype "passive"))
    )
    (net (code "77") (name "unconnected-(J6-36-PadA18)") (class "Default")
      (node (ref "J6") (pin "A18") (pinfunction "36_A18") (pintype "passive"))
    )
    (net (code "78") (name "unconnected-(J6-39-PadB20)") (class "Default")
      (node (ref "J6") (pin "B20") (pinfunction "39_B20") (pintype "passive"))
    )
    (net (code "79") (name "unconnected-(J7-15-PadB8)") (class "Default")
      (node (ref "J7") (pin "B8") (pinfunction "15_B8") (pintype "passive"))
    )
    (net (code "80") (name "unconnected-(J7-17-PadB9)") (class "Default")
      (node (ref "J7") (pin "B9") (pinfunction "17_B9") (pintype "passive"))
    )
    (net (code "81") (name "unconnected-(J7-19-PadB10)") (class "Default")
      (node (ref "J7") (pin "B10") (pinfunction "19_B10") (pintype "passive"))
    )
    (net (code "82") (name "unconnected-(J7-21-PadB11)") (class "Default")
      (node (ref "J7") (pin "B11") (pinfunction "21_B11") (pintype "passive"))
    )
    (net (code "83") (name "unconnected-(J7-23-PadB12)") (class "Default")
      (node (ref "J7") (pin "B12") (pinfunction "23_B12") (pintype "passive"))
    )
    (net (code "84") (name "unconnected-(J7-30-PadA15)") (class "Default")
      (node (ref "J7") (pin "A15") (pinfunction "30_A15") (pintype "passive"))
    )
    (net (code "85") (name "unconnected-(J7-34-PadA17)") (class "Default")
      (node (ref "J7") (pin "A17") (pinfunction "34_A17") (pintype "passive"))
    )
    (net (code "86") (name "unconnected-(J7-36-PadA18)") (class "Default")
      (node (ref "J7") (pin "A18") (pinfunction "36_A18") (pintype "passive"))
    )
    (net (code "87") (name "unconnected-(J7-39-PadB20)") (class "Default")
      (node (ref "J7") (pin "B20") (pinfunction "39_B20") (pintype "passive"))
    )
  )
)
